# Pi_SD_CARD.net
KiCad netlist of a schematic drawn in Altium Designer
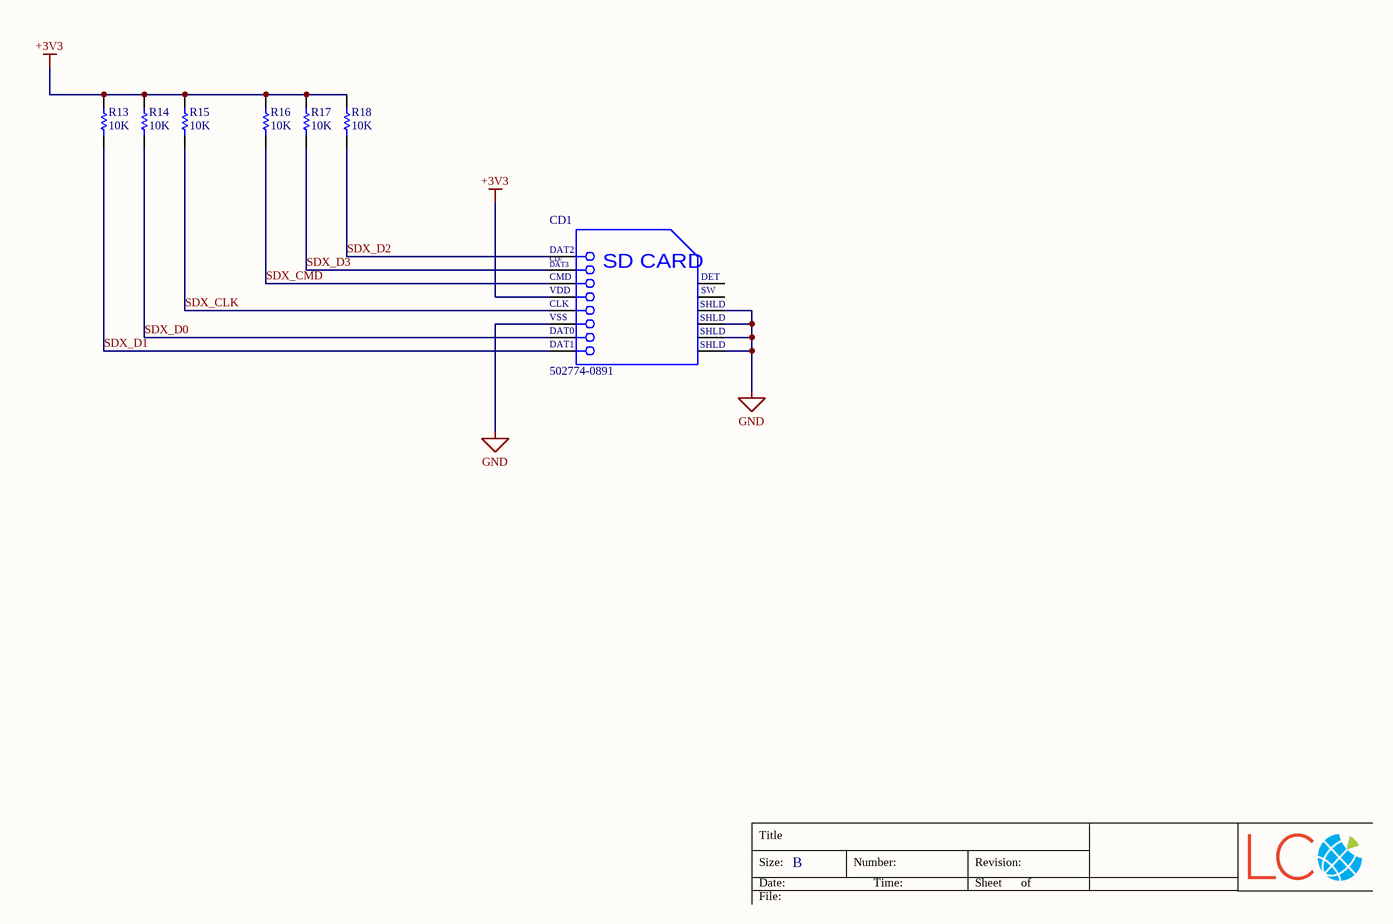
[diagram p0: Pi_SD_CARD.SchDoc]

(export (version "E")
  (design (tool "Eeschema 10.0.6"))
  (components
    (comp (ref "CD1")
      (value "502774-0891")
      (footprint "MOLX-502774-0891_V")
      (description "Micro SD Memory Card Connector, 0.5 A, 10 V (DC), -25 to 85 degC, 8-Pin SMT, RoHS, Tape and Reel")
      (fields (field (name "MANUFACTURER") "Molex"))
      (libsource (lib "Altium Content Vault") (part "CN-SD-8-2SW-4S_B"))
    )
    (comp (ref "R13")
      (value "10K")
      (footprint "RESC1005X40X25NL05T05")
      (description "CRCW040210K0FKED")
      (fields (field (name "MANUFACTURER") "Vishay Dale"))
      (libsource (lib "Altium Content Vault") (part "RES"))
    )
    (comp (ref "R14")
      (value "10K")
      (footprint "RESC1005X40X25NL05T05")
      (description "CRCW040210K0FKED")
      (fields (field (name "MANUFACTURER") "Vishay Dale"))
      (libsource (lib "Altium Content Vault") (part "RES"))
    )
    (comp (ref "R15")
      (value "10K")
      (footprint "RESC1005X40X25NL05T05")
      (description "CRCW040210K0FKED")
      (fields (field (name "MANUFACTURER") "Vishay Dale"))
      (libsource (lib "Altium Content Vault") (part "RES"))
    )
    (comp (ref "R16")
      (value "10K")
      (footprint "RESC1005X40X25NL05T05")
      (description "CRCW040210K0FKED")
      (fields (field (name "MANUFACTURER") "Vishay Dale"))
      (libsource (lib "Altium Content Vault") (part "RES"))
    )
    (comp (ref "R17")
      (value "10K")
      (footprint "RESC1005X40X25NL05T05")
      (description "CRCW040210K0FKED")
      (fields (field (name "MANUFACTURER") "Vishay Dale"))
      (libsource (lib "Altium Content Vault") (part "RES"))
    )
    (comp (ref "R18")
      (value "10K")
      (footprint "RESC1005X40X25NL05T05")
      (description "CRCW040210K0FKED")
      (fields (field (name "MANUFACTURER") "Vishay Dale"))
      (libsource (lib "Altium Content Vault") (part "RES"))
    )
  )
  (nets
    (net (code "1") (name "+3V3") (class "Default")
      (node (ref "CD1") (pin "4") (pinfunction "VDD_4") (pintype "passive"))
      (node (ref "R13") (pin "2") (pinfunction "2_2") (pintype "passive"))
      (node (ref "R14") (pin "2") (pinfunction "2_2") (pintype "passive"))
      (node (ref "R15") (pin "2") (pinfunction "2_2") (pintype "passive"))
      (node (ref "R16") (pin "2") (pinfunction "2_2") (pintype "passive"))
      (node (ref "R17") (pin "2") (pinfunction "2_2") (pintype "passive"))
      (node (ref "R18") (pin "2") (pinfunction "2_2") (pintype "passive"))
    )
    (net (code "2") (name "/SDX_CLK") (class "Default")
      (node (ref "CD1") (pin "5") (pinfunction "CLK_5") (pintype "passive"))
      (node (ref "R15") (pin "1") (pinfunction "1_1") (pintype "passive"))
    )
    (net (code "3") (name "/SDX_CMD") (class "Default")
      (node (ref "CD1") (pin "3") (pinfunction "CMD_3") (pintype "passive"))
      (node (ref "R16") (pin "1") (pinfunction "1_1") (pintype "passive"))
    )
    (net (code "4") (name "/SDX_D0") (class "Default")
      (node (ref "CD1") (pin "7") (pinfunction "DAT0_7") (pintype "passive"))
      (node (ref "R14") (pin "1") (pinfunction "1_1") (pintype "passive"))
    )
    (net (code "5") (name "/SDX_D1") (class "Default")
      (node (ref "CD1") (pin "8") (pinfunction "DAT1_8") (pintype "passive"))
      (node (ref "R13") (pin "1") (pinfunction "1_1") (pintype "passive"))
    )
    (net (code "6") (name "/SDX_D2") (class "Default")
      (node (ref "CD1") (pin "1") (pinfunction "DAT2_1") (pintype "passive"))
      (node (ref "R18") (pin "1") (pinfunction "1_1") (pintype "passive"))
    )
    (net (code "7") (name "/SDX_D3") (class "Default")
      (node (ref "CD1") (pin "2") (pinfunction "CD/DAT3_2") (pintype "passive"))
      (node (ref "R17") (pin "1") (pinfunction "1_1") (pintype "passive"))
    )
    (net (code "8") (name "GND") (class "Default")
      (node (ref "CD1") (pin "11") (pinfunction "SHLD_11") (pintype "passive"))
      (node (ref "CD1") (pin "12") (pinfunction "SHLD_12") (pintype "passive"))
      (node (ref "CD1") (pin "13") (pinfunction "SHLD_13") (pintype "passive"))
      (node (ref "CD1") (pin "14") (pinfunction "SHLD_14") (pintype "passive"))
      (node (ref "CD1") (pin "6") (pinfunction "VSS_6") (pintype "passive"))
    )
    (net (code "9") (name "unconnected-(CD1-DETECT-Pad9)") (class "Default")
      (node (ref "CD1") (pin "9") (pinfunction "DETECT_9") (pintype "passive"))
    )
    (net (code "10") (name "unconnected-(CD1-SWITCH-Pad10)") (class "Default")
      (node (ref "CD1") (pin "10") (pinfunction "SWITCH_10") (pintype "passive"))
    )
  )
)
